# Licznik_mili_sekund.net
KiCad netlist of a schematic drawn in Altium Designer
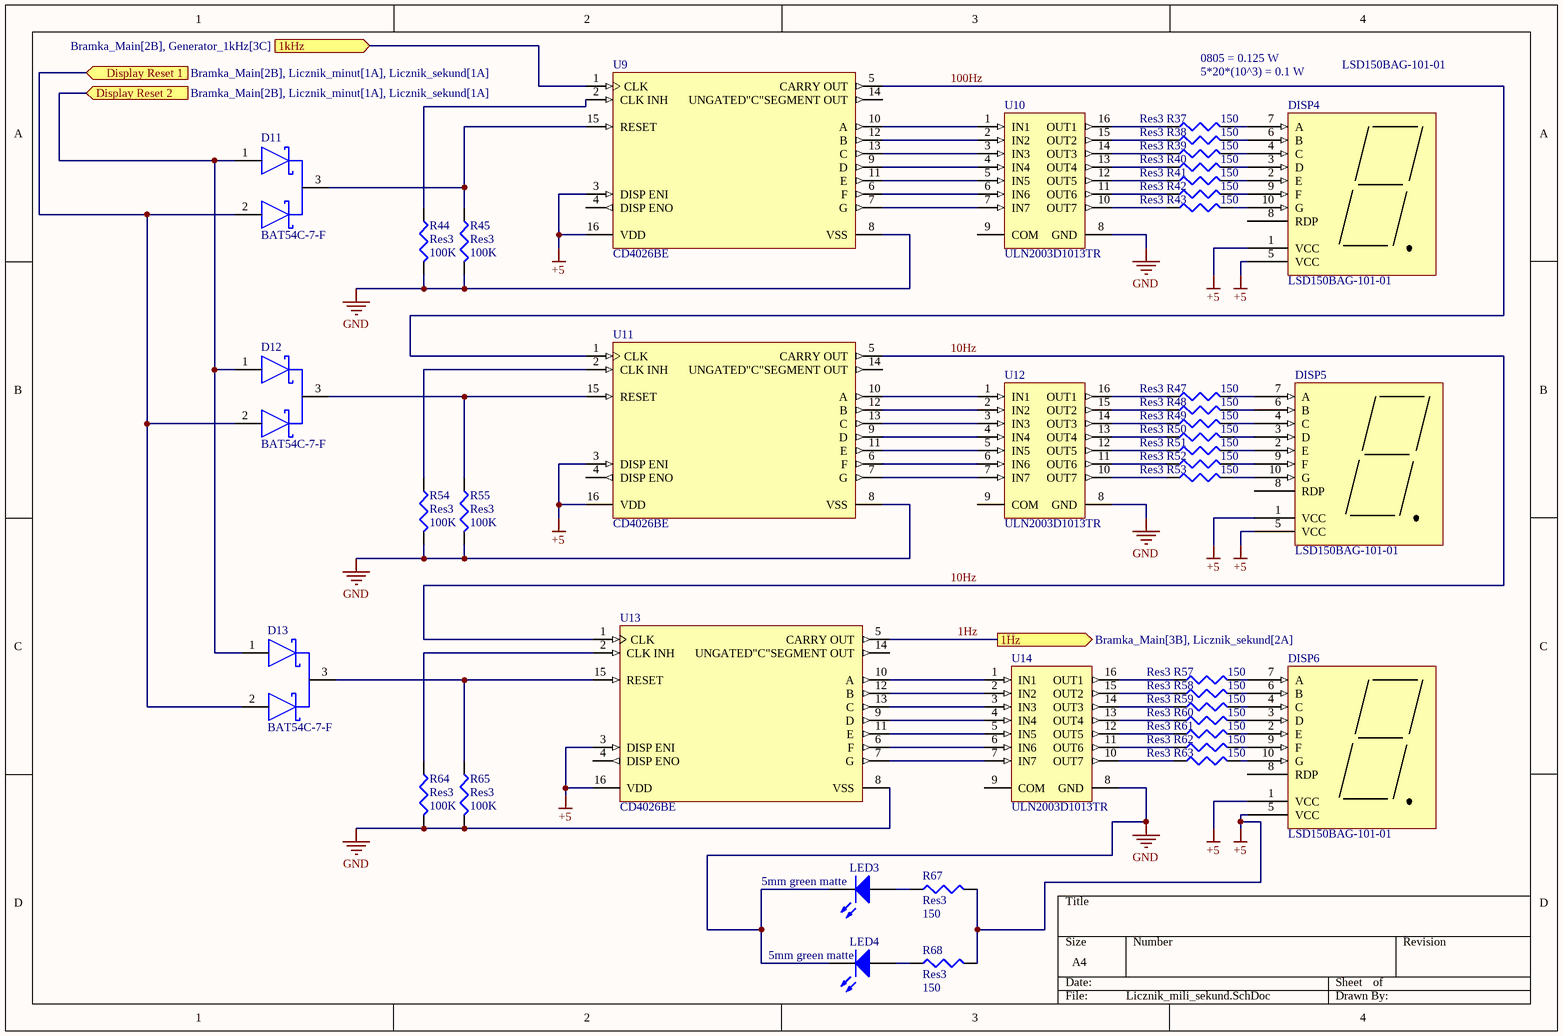
[diagram p0: Licznik_mili_sekund.SchDoc]

(export (version "E")
  (design (tool "Eeschema 10.0.6"))
  (components
    (comp (ref "D11")
      (value "BAT54C-7-F")
      (footprint "FP-SOT23-IPC_B")
      (description "DIODE ARRAY SCHOTTKY 30V SOT23-3")
      (libsource (lib "Altium Content Vault") (part "3eac2aa0c1ac86323ecc23460aa29c6"))
    )
    (comp (ref "D12")
      (value "BAT54C-7-F")
      (footprint "FP-SOT23-IPC_B")
      (description "DIODE ARRAY SCHOTTKY 30V SOT23-3")
      (libsource (lib "Altium Content Vault") (part "3eac2aa0c1ac86323ecc23460aa29c6"))
    )
    (comp (ref "D13")
      (value "BAT54C-7-F")
      (footprint "FP-SOT23-IPC_B")
      (description "DIODE ARRAY SCHOTTKY 30V SOT23-3")
      (libsource (lib "Altium Content Vault") (part "3eac2aa0c1ac86323ecc23460aa29c6"))
    )
    (comp (ref "DISP4")
      (value "LSD150BAG-101-01")
      (footprint "7 segment display")
      (description "7 segment display 1.5 inch")
      (libsource (lib "WUST") (part "LSD150BAG-101-01-Symbol-1"))
    )
    (comp (ref "DISP5")
      (value "LSD150BAG-101-01")
      (footprint "7 segment display")
      (description "7 segment display 1.5 inch")
      (libsource (lib "WUST") (part "LSD150BAG-101-01-Symbol-1"))
    )
    (comp (ref "DISP6")
      (value "LSD150BAG-101-01")
      (footprint "7 segment display")
      (description "7 segment display 1.5 inch")
      (libsource (lib "WUST") (part "LSD150BAG-101-01-Symbol-1"))
    )
    (comp (ref "LED3")
      (value "5mm green matte")
      (footprint "Type 5mm")
      (description "THT LED round mono-color color lens, WL-TMRW, Bright Green")
      (fields (field (name "PARTNUMBER") "151051VS04000") (field (name "MANUFACTURER") "Wuerth Elektronik"))
      (libsource (lib "Altium Content Vault") (part "WE-LED_K1A2-2"))
    )
    (comp (ref "LED4")
      (value "5mm green matte")
      (footprint "Type 5mm")
      (description "THT LED round mono-color color lens, WL-TMRW, Bright Green")
      (fields (field (name "PARTNUMBER") "151051VS04000") (field (name "MANUFACTURER") "Wuerth Elektronik"))
      (libsource (lib "Altium Content Vault") (part "WE-LED_K1A2-2"))
    )
    (comp (ref "R37")
      (value "Res3")
      (footprint "6-0805_M")
      (description "Resistor")
      (fields (field (name "ALTIUM_VALUE") "150") (field (name "PUBLISHER") "Altium Limited"))
      (libsource (lib "Miscellaneous Devices") (part "Res3"))
    )
    (comp (ref "R38")
      (value "Res3")
      (footprint "6-0805_M")
      (description "Resistor")
      (fields (field (name "ALTIUM_VALUE") "150") (field (name "PUBLISHER") "Altium Limited"))
      (libsource (lib "Miscellaneous Devices") (part "Res3"))
    )
    (comp (ref "R39")
      (value "Res3")
      (footprint "6-0805_M")
      (description "Resistor")
      (fields (field (name "ALTIUM_VALUE") "150") (field (name "PUBLISHER") "Altium Limited"))
      (libsource (lib "Miscellaneous Devices") (part "Res3"))
    )
    (comp (ref "R40")
      (value "Res3")
      (footprint "6-0805_M")
      (description "Resistor")
      (fields (field (name "ALTIUM_VALUE") "150") (field (name "PUBLISHER") "Altium Limited"))
      (libsource (lib "Miscellaneous Devices") (part "Res3"))
    )
    (comp (ref "R41")
      (value "Res3")
      (footprint "6-0805_M")
      (description "Resistor")
      (fields (field (name "ALTIUM_VALUE") "150") (field (name "PUBLISHER") "Altium Limited"))
      (libsource (lib "Miscellaneous Devices") (part "Res3"))
    )
    (comp (ref "R42")
      (value "Res3")
      (footprint "6-0805_M")
      (description "Resistor")
      (fields (field (name "ALTIUM_VALUE") "150") (field (name "PUBLISHER") "Altium Limited"))
      (libsource (lib "Miscellaneous Devices") (part "Res3"))
    )
    (comp (ref "R43")
      (value "Res3")
      (footprint "6-0805_M")
      (description "Resistor")
      (fields (field (name "ALTIUM_VALUE") "150") (field (name "PUBLISHER") "Altium Limited"))
      (libsource (lib "Miscellaneous Devices") (part "Res3"))
    )
    (comp (ref "R44")
      (value "Res3")
      (footprint "J1-0603")
      (description "Resistor")
      (fields (field (name "ALTIUM_VALUE") "100K") (field (name "PUBLISHER") "Altium Limited"))
      (libsource (lib "Miscellaneous Devices") (part "Res3"))
    )
    (comp (ref "R45")
      (value "Res3")
      (footprint "J1-0603")
      (description "Resistor")
      (fields (field (name "ALTIUM_VALUE") "100K") (field (name "PUBLISHER") "Altium Limited"))
      (libsource (lib "Miscellaneous Devices") (part "Res3"))
    )
    (comp (ref "R47")
      (value "Res3")
      (footprint "6-0805_M")
      (description "Resistor")
      (fields (field (name "ALTIUM_VALUE") "150") (field (name "PUBLISHER") "Altium Limited"))
      (libsource (lib "Miscellaneous Devices") (part "Res3"))
    )
    (comp (ref "R48")
      (value "Res3")
      (footprint "6-0805_M")
      (description "Resistor")
      (fields (field (name "ALTIUM_VALUE") "150") (field (name "PUBLISHER") "Altium Limited"))
      (libsource (lib "Miscellaneous Devices") (part "Res3"))
    )
    (comp (ref "R49")
      (value "Res3")
      (footprint "6-0805_M")
      (description "Resistor")
      (fields (field (name "ALTIUM_VALUE") "150") (field (name "PUBLISHER") "Altium Limited"))
      (libsource (lib "Miscellaneous Devices") (part "Res3"))
    )
    (comp (ref "R50")
      (value "Res3")
      (footprint "6-0805_M")
      (description "Resistor")
      (fields (field (name "ALTIUM_VALUE") "150") (field (name "PUBLISHER") "Altium Limited"))
      (libsource (lib "Miscellaneous Devices") (part "Res3"))
    )
    (comp (ref "R51")
      (value "Res3")
      (footprint "6-0805_M")
      (description "Resistor")
      (fields (field (name "ALTIUM_VALUE") "150") (field (name "PUBLISHER") "Altium Limited"))
      (libsource (lib "Miscellaneous Devices") (part "Res3"))
    )
    (comp (ref "R52")
      (value "Res3")
      (footprint "6-0805_M")
      (description "Resistor")
      (fields (field (name "ALTIUM_VALUE") "150") (field (name "PUBLISHER") "Altium Limited"))
      (libsource (lib "Miscellaneous Devices") (part "Res3"))
    )
    (comp (ref "R53")
      (value "Res3")
      (footprint "6-0805_M")
      (description "Resistor")
      (fields (field (name "ALTIUM_VALUE") "150") (field (name "PUBLISHER") "Altium Limited"))
      (libsource (lib "Miscellaneous Devices") (part "Res3"))
    )
    (comp (ref "R54")
      (value "Res3")
      (footprint "J1-0603")
      (description "Resistor")
      (fields (field (name "ALTIUM_VALUE") "100K") (field (name "PUBLISHER") "Altium Limited"))
      (libsource (lib "Miscellaneous Devices") (part "Res3"))
    )
    (comp (ref "R55")
      (value "Res3")
      (footprint "J1-0603")
      (description "Resistor")
      (fields (field (name "ALTIUM_VALUE") "100K") (field (name "PUBLISHER") "Altium Limited"))
      (libsource (lib "Miscellaneous Devices") (part "Res3"))
    )
    (comp (ref "R57")
      (value "Res3")
      (footprint "6-0805_M")
      (description "Resistor")
      (fields (field (name "ALTIUM_VALUE") "150") (field (name "PUBLISHER") "Altium Limited"))
      (libsource (lib "Miscellaneous Devices") (part "Res3"))
    )
    (comp (ref "R58")
      (value "Res3")
      (footprint "6-0805_M")
      (description "Resistor")
      (fields (field (name "ALTIUM_VALUE") "150") (field (name "PUBLISHER") "Altium Limited"))
      (libsource (lib "Miscellaneous Devices") (part "Res3"))
    )
    (comp (ref "R59")
      (value "Res3")
      (footprint "6-0805_M")
      (description "Resistor")
      (fields (field (name "ALTIUM_VALUE") "150") (field (name "PUBLISHER") "Altium Limited"))
      (libsource (lib "Miscellaneous Devices") (part "Res3"))
    )
    (comp (ref "R60")
      (value "Res3")
      (footprint "6-0805_M")
      (description "Resistor")
      (fields (field (name "ALTIUM_VALUE") "150") (field (name "PUBLISHER") "Altium Limited"))
      (libsource (lib "Miscellaneous Devices") (part "Res3"))
    )
    (comp (ref "R61")
      (value "Res3")
      (footprint "6-0805_M")
      (description "Resistor")
      (fields (field (name "ALTIUM_VALUE") "150") (field (name "PUBLISHER") "Altium Limited"))
      (libsource (lib "Miscellaneous Devices") (part "Res3"))
    )
    (comp (ref "R62")
      (value "Res3")
      (footprint "6-0805_M")
      (description "Resistor")
      (fields (field (name "ALTIUM_VALUE") "150") (field (name "PUBLISHER") "Altium Limited"))
      (libsource (lib "Miscellaneous Devices") (part "Res3"))
    )
    (comp (ref "R63")
      (value "Res3")
      (footprint "6-0805_M")
      (description "Resistor")
      (fields (field (name "ALTIUM_VALUE") "150") (field (name "PUBLISHER") "Altium Limited"))
      (libsource (lib "Miscellaneous Devices") (part "Res3"))
    )
    (comp (ref "R64")
      (value "Res3")
      (footprint "J1-0603")
      (description "Resistor")
      (fields (field (name "ALTIUM_VALUE") "100K") (field (name "PUBLISHER") "Altium Limited"))
      (libsource (lib "Miscellaneous Devices") (part "Res3"))
    )
    (comp (ref "R65")
      (value "Res3")
      (footprint "J1-0603")
      (description "Resistor")
      (fields (field (name "ALTIUM_VALUE") "100K") (field (name "PUBLISHER") "Altium Limited"))
      (libsource (lib "Miscellaneous Devices") (part "Res3"))
    )
    (comp (ref "R67")
      (value "Res3")
      (footprint "6-0805_M")
      (description "Resistor")
      (fields (field (name "ALTIUM_VALUE") "150") (field (name "PUBLISHER") "Altium Limited"))
      (libsource (lib "Miscellaneous Devices") (part "Res3"))
    )
    (comp (ref "R68")
      (value "Res3")
      (footprint "6-0805_M")
      (description "Resistor")
      (fields (field (name "ALTIUM_VALUE") "150") (field (name "PUBLISHER") "Altium Limited"))
      (libsource (lib "Miscellaneous Devices") (part "Res3"))
    )
    (comp (ref "U9")
      (value "CD4026BE")
      (footprint "N0016A")
      (fields
        (field (name "MANUFACTURER") "Texas Instruments")
        (field (name "GENERIC PART NUMBER") "CD4026B")
      )
      (libsource (lib "Altium Content Vault") (part "TI-CD4026B-16"))
    )
    (comp (ref "U10")
      (value "ULN2003D1013TR")
      (footprint "STM-SO-16_M")
      (fields (field (name "MANUFACTURER") "STMicroelectronics"))
      (libsource (lib "Altium Content Vault") (part "STM-ULN2003A-PDIP-16"))
    )
    (comp (ref "U11")
      (value "CD4026BE")
      (footprint "N0016A")
      (fields
        (field (name "MANUFACTURER") "Texas Instruments")
        (field (name "GENERIC PART NUMBER") "CD4026B")
      )
      (libsource (lib "Altium Content Vault") (part "TI-CD4026B-16"))
    )
    (comp (ref "U12")
      (value "ULN2003D1013TR")
      (footprint "STM-SO-16_M")
      (fields (field (name "MANUFACTURER") "STMicroelectronics"))
      (libsource (lib "Altium Content Vault") (part "STM-ULN2003A-PDIP-16"))
    )
    (comp (ref "U13")
      (value "CD4026BE")
      (footprint "N0016A")
      (fields
        (field (name "MANUFACTURER") "Texas Instruments")
        (field (name "GENERIC PART NUMBER") "CD4026B")
      )
      (libsource (lib "Altium Content Vault") (part "TI-CD4026B-16"))
    )
    (comp (ref "U14")
      (value "ULN2003D1013TR")
      (footprint "STM-SO-16_M")
      (fields (field (name "MANUFACTURER") "STMicroelectronics"))
      (libsource (lib "Altium Content Vault") (part "STM-ULN2003A-PDIP-16"))
    )
  )
  (nets
    (net (code "1") (name "+5") (class "Default")
      (node (ref "DISP4") (pin "1") (pinfunction "VCC_1") (pintype "power_in"))
      (node (ref "DISP4") (pin "5") (pinfunction "VCC_5") (pintype "power_in"))
      (node (ref "DISP5") (pin "1") (pinfunction "VCC_1") (pintype "power_in"))
      (node (ref "DISP5") (pin "5") (pinfunction "VCC_5") (pintype "power_in"))
      (node (ref "DISP6") (pin "1") (pinfunction "VCC_1") (pintype "power_in"))
      (node (ref "DISP6") (pin "5") (pinfunction "VCC_5") (pintype "power_in"))
      (node (ref "R67") (pin "2") (pinfunction "2_2") (pintype "passive"))
      (node (ref "R68") (pin "2") (pinfunction "2_2") (pintype "passive"))
      (node (ref "U11") (pin "16") (pinfunction "VDD_16") (pintype "power_in"))
      (node (ref "U11") (pin "3") (pinfunction "DISP_ENI_3") (pintype "input"))
      (node (ref "U13") (pin "16") (pinfunction "VDD_16") (pintype "power_in"))
      (node (ref "U13") (pin "3") (pinfunction "DISP_ENI_3") (pintype "input"))
      (node (ref "U9") (pin "16") (pinfunction "VDD_16") (pintype "power_in"))
      (node (ref "U9") (pin "3") (pinfunction "DISP_ENI_3") (pintype "input"))
    )
    (net (code "2") (name "/1Hz") (class "Default")
      (node (ref "U13") (pin "5") (pinfunction "CARRY_OUT_5") (pintype "output"))
    )
    (net (code "3") (name "/1kHz") (class "Default")
      (node (ref "U9") (pin "1") (pinfunction "CLK_1") (pintype "input"))
    )
    (net (code "4") (name "/10Hz") (class "Default")
      (node (ref "U11") (pin "5") (pinfunction "CARRY_OUT_5") (pintype "output"))
      (node (ref "U13") (pin "1") (pinfunction "CLK_1") (pintype "input"))
    )
    (net (code "5") (name "/100Hz") (class "Default")
      (node (ref "U11") (pin "1") (pinfunction "CLK_1") (pintype "input"))
      (node (ref "U9") (pin "5") (pinfunction "CARRY_OUT_5") (pintype "output"))
    )
    (net (code "6") (name "/Display Reset 1") (class "Default")
      (node (ref "D11") (pin "2") (pinfunction "2_ANODE_2") (pintype "passive"))
      (node (ref "D12") (pin "2") (pinfunction "2_ANODE_2") (pintype "passive"))
      (node (ref "D13") (pin "2") (pinfunction "2_ANODE_2") (pintype "passive"))
    )
    (net (code "7") (name "/Display Reset 2") (class "Default")
      (node (ref "D11") (pin "1") (pinfunction "1_ANODE_1") (pintype "passive"))
      (node (ref "D12") (pin "1") (pinfunction "1_ANODE_1") (pintype "passive"))
      (node (ref "D13") (pin "1") (pinfunction "1_ANODE_1") (pintype "passive"))
    )
    (net (code "8") (name "GND") (class "Default")
      (node (ref "LED3") (pin "1") (pinfunction "K_1") (pintype "passive"))
      (node (ref "LED4") (pin "1") (pinfunction "K_1") (pintype "passive"))
      (node (ref "R44") (pin "2") (pinfunction "2_2") (pintype "passive"))
      (node (ref "R45") (pin "2") (pinfunction "2_2") (pintype "passive"))
      (node (ref "R54") (pin "2") (pinfunction "2_2") (pintype "passive"))
      (node (ref "R55") (pin "2") (pinfunction "2_2") (pintype "passive"))
      (node (ref "R64") (pin "2") (pinfunction "2_2") (pintype "passive"))
      (node (ref "R65") (pin "2") (pinfunction "2_2") (pintype "passive"))
      (node (ref "U10") (pin "8") (pinfunction "GND_8") (pintype "power_in"))
      (node (ref "U11") (pin "8") (pinfunction "VSS_8") (pintype "power_in"))
      (node (ref "U12") (pin "8") (pinfunction "GND_8") (pintype "power_in"))
      (node (ref "U13") (pin "8") (pinfunction "VSS_8") (pintype "power_in"))
      (node (ref "U14") (pin "8") (pinfunction "GND_8") (pintype "power_in"))
      (node (ref "U9") (pin "8") (pinfunction "VSS_8") (pintype "power_in"))
    )
    (net (code "9") (name "Net-(D11-COMMON_CATHODE)") (class "Default")
      (node (ref "D11") (pin "3") (pinfunction "COMMON_CATHODE_3") (pintype "passive"))
      (node (ref "R45") (pin "1") (pinfunction "1_1") (pintype "passive"))
      (node (ref "U9") (pin "15") (pinfunction "RESET_15") (pintype "input"))
    )
    (net (code "10") (name "Net-(D12-COMMON_CATHODE)") (class "Default")
      (node (ref "D12") (pin "3") (pinfunction "COMMON_CATHODE_3") (pintype "passive"))
      (node (ref "R55") (pin "1") (pinfunction "1_1") (pintype "passive"))
      (node (ref "U11") (pin "15") (pinfunction "RESET_15") (pintype "input"))
    )
    (net (code "11") (name "Net-(D13-COMMON_CATHODE)") (class "Default")
      (node (ref "D13") (pin "3") (pinfunction "COMMON_CATHODE_3") (pintype "passive"))
      (node (ref "R65") (pin "1") (pinfunction "1_1") (pintype "passive"))
      (node (ref "U13") (pin "15") (pinfunction "RESET_15") (pintype "input"))
    )
    (net (code "12") (name "Net-(DISP4-A)") (class "Default")
      (node (ref "DISP4") (pin "7") (pinfunction "A_7") (pintype "input"))
      (node (ref "R37") (pin "2") (pinfunction "2_2") (pintype "passive"))
    )
    (net (code "13") (name "Net-(DISP4-B)") (class "Default")
      (node (ref "DISP4") (pin "6") (pinfunction "B_6") (pintype "input"))
      (node (ref "R38") (pin "2") (pinfunction "2_2") (pintype "passive"))
    )
    (net (code "14") (name "Net-(DISP4-C)") (class "Default")
      (node (ref "DISP4") (pin "4") (pinfunction "C_4") (pintype "input"))
      (node (ref "R39") (pin "2") (pinfunction "2_2") (pintype "passive"))
    )
    (net (code "15") (name "Net-(DISP4-D)") (class "Default")
      (node (ref "DISP4") (pin "3") (pinfunction "D_3") (pintype "input"))
      (node (ref "R40") (pin "2") (pinfunction "2_2") (pintype "passive"))
    )
    (net (code "16") (name "Net-(DISP4-E)") (class "Default")
      (node (ref "DISP4") (pin "2") (pinfunction "E_2") (pintype "input"))
      (node (ref "R41") (pin "2") (pinfunction "2_2") (pintype "passive"))
    )
    (net (code "17") (name "Net-(DISP4-F)") (class "Default")
      (node (ref "DISP4") (pin "9") (pinfunction "F_9") (pintype "input"))
      (node (ref "R42") (pin "2") (pinfunction "2_2") (pintype "passive"))
    )
    (net (code "18") (name "Net-(DISP4-G)") (class "Default")
      (node (ref "DISP4") (pin "10") (pinfunction "G_10") (pintype "input"))
      (node (ref "R43") (pin "2") (pinfunction "2_2") (pintype "passive"))
    )
    (net (code "19") (name "Net-(DISP5-A)") (class "Default")
      (node (ref "DISP5") (pin "7") (pinfunction "A_7") (pintype "input"))
      (node (ref "R47") (pin "2") (pinfunction "2_2") (pintype "passive"))
    )
    (net (code "20") (name "Net-(DISP5-B)") (class "Default")
      (node (ref "DISP5") (pin "6") (pinfunction "B_6") (pintype "input"))
      (node (ref "R48") (pin "2") (pinfunction "2_2") (pintype "passive"))
    )
    (net (code "21") (name "Net-(DISP5-C)") (class "Default")
      (node (ref "DISP5") (pin "4") (pinfunction "C_4") (pintype "input"))
      (node (ref "R49") (pin "2") (pinfunction "2_2") (pintype "passive"))
    )
    (net (code "22") (name "Net-(DISP5-D)") (class "Default")
      (node (ref "DISP5") (pin "3") (pinfunction "D_3") (pintype "input"))
      (node (ref "R50") (pin "2") (pinfunction "2_2") (pintype "passive"))
    )
    (net (code "23") (name "Net-(DISP5-E)") (class "Default")
      (node (ref "DISP5") (pin "2") (pinfunction "E_2") (pintype "input"))
      (node (ref "R51") (pin "2") (pinfunction "2_2") (pintype "passive"))
    )
    (net (code "24") (name "Net-(DISP5-F)") (class "Default")
      (node (ref "DISP5") (pin "9") (pinfunction "F_9") (pintype "input"))
      (node (ref "R52") (pin "2") (pinfunction "2_2") (pintype "passive"))
    )
    (net (code "25") (name "Net-(DISP5-G)") (class "Default")
      (node (ref "DISP5") (pin "10") (pinfunction "G_10") (pintype "input"))
      (node (ref "R53") (pin "2") (pinfunction "2_2") (pintype "passive"))
    )
    (net (code "26") (name "Net-(DISP6-A)") (class "Default")
      (node (ref "DISP6") (pin "7") (pinfunction "A_7") (pintype "input"))
      (node (ref "R57") (pin "2") (pinfunction "2_2") (pintype "passive"))
    )
    (net (code "27") (name "Net-(DISP6-B)") (class "Default")
      (node (ref "DISP6") (pin "6") (pinfunction "B_6") (pintype "input"))
      (node (ref "R58") (pin "2") (pinfunction "2_2") (pintype "passive"))
    )
    (net (code "28") (name "Net-(DISP6-C)") (class "Default")
      (node (ref "DISP6") (pin "4") (pinfunction "C_4") (pintype "input"))
      (node (ref "R59") (pin "2") (pinfunction "2_2") (pintype "passive"))
    )
    (net (code "29") (name "Net-(DISP6-D)") (class "Default")
      (node (ref "DISP6") (pin "3") (pinfunction "D_3") (pintype "input"))
      (node (ref "R60") (pin "2") (pinfunction "2_2") (pintype "passive"))
    )
    (net (code "30") (name "Net-(DISP6-E)") (class "Default")
      (node (ref "DISP6") (pin "2") (pinfunction "E_2") (pintype "input"))
      (node (ref "R61") (pin "2") (pinfunction "2_2") (pintype "passive"))
    )
    (net (code "31") (name "Net-(DISP6-F)") (class "Default")
      (node (ref "DISP6") (pin "9") (pinfunction "F_9") (pintype "input"))
      (node (ref "R62") (pin "2") (pinfunction "2_2") (pintype "passive"))
    )
    (net (code "32") (name "Net-(DISP6-G)") (class "Default")
      (node (ref "DISP6") (pin "10") (pinfunction "G_10") (pintype "input"))
      (node (ref "R63") (pin "2") (pinfunction "2_2") (pintype "passive"))
    )
    (net (code "33") (name "Net-(LED3-A)") (class "Default")
      (node (ref "LED3") (pin "2") (pinfunction "A_2") (pintype "passive"))
      (node (ref "R67") (pin "1") (pinfunction "1_1") (pintype "passive"))
    )
    (net (code "34") (name "Net-(LED4-A)") (class "Default")
      (node (ref "LED4") (pin "2") (pinfunction "A_2") (pintype "passive"))
      (node (ref "R68") (pin "1") (pinfunction "1_1") (pintype "passive"))
    )
    (net (code "35") (name "Net-(U9-CLK_INH)") (class "Default")
      (node (ref "R44") (pin "1") (pinfunction "1_1") (pintype "passive"))
      (node (ref "U9") (pin "2") (pinfunction "CLK_INH_2") (pintype "input"))
    )
    (net (code "36") (name "Net-(U10-IN1)") (class "Default")
      (node (ref "U10") (pin "1") (pinfunction "IN1_1") (pintype "input"))
      (node (ref "U9") (pin "10") (pinfunction "A_10") (pintype "output"))
    )
    (net (code "37") (name "Net-(U10-IN2)") (class "Default")
      (node (ref "U10") (pin "2") (pinfunction "IN2_2") (pintype "input"))
      (node (ref "U9") (pin "12") (pinfunction "B_12") (pintype "output"))
    )
    (net (code "38") (name "Net-(U10-IN3)") (class "Default")
      (node (ref "U10") (pin "3") (pinfunction "IN3_3") (pintype "input"))
      (node (ref "U9") (pin "13") (pinfunction "C_13") (pintype "output"))
    )
    (net (code "39") (name "Net-(U10-IN4)") (class "Default")
      (node (ref "U10") (pin "4") (pinfunction "IN4_4") (pintype "input"))
      (node (ref "U9") (pin "9") (pinfunction "D_9") (pintype "output"))
    )
    (net (code "40") (name "Net-(U10-IN5)") (class "Default")
      (node (ref "U10") (pin "5") (pinfunction "IN5_5") (pintype "input"))
      (node (ref "U9") (pin "11") (pinfunction "E_11") (pintype "output"))
    )
    (net (code "41") (name "Net-(U10-IN6)") (class "Default")
      (node (ref "U10") (pin "6") (pinfunction "IN6_6") (pintype "input"))
      (node (ref "U9") (pin "6") (pinfunction "F_6") (pintype "output"))
    )
    (net (code "42") (name "Net-(U10-IN7)") (class "Default")
      (node (ref "U10") (pin "7") (pinfunction "IN7_7") (pintype "input"))
      (node (ref "U9") (pin "7") (pinfunction "G_7") (pintype "output"))
    )
    (net (code "43") (name "Net-(U10-OUT1)") (class "Default")
      (node (ref "R37") (pin "1") (pinfunction "1_1") (pintype "passive"))
      (node (ref "U10") (pin "16") (pinfunction "OUT1_16") (pintype "output"))
    )
    (net (code "44") (name "Net-(U10-OUT2)") (class "Default")
      (node (ref "R38") (pin "1") (pinfunction "1_1") (pintype "passive"))
      (node (ref "U10") (pin "15") (pinfunction "OUT2_15") (pintype "output"))
    )
    (net (code "45") (name "Net-(U10-OUT3)") (class "Default")
      (node (ref "R39") (pin "1") (pinfunction "1_1") (pintype "passive"))
      (node (ref "U10") (pin "14") (pinfunction "OUT3_14") (pintype "output"))
    )
    (net (code "46") (name "Net-(U10-OUT4)") (class "Default")
      (node (ref "R40") (pin "1") (pinfunction "1_1") (pintype "passive"))
      (node (ref "U10") (pin "13") (pinfunction "OUT4_13") (pintype "output"))
    )
    (net (code "47") (name "Net-(U10-OUT5)") (class "Default")
      (node (ref "R41") (pin "1") (pinfunction "1_1") (pintype "passive"))
      (node (ref "U10") (pin "12") (pinfunction "OUT5_12") (pintype "output"))
    )
    (net (code "48") (name "Net-(U10-OUT6)") (class "Default")
      (node (ref "R42") (pin "1") (pinfunction "1_1") (pintype "passive"))
      (node (ref "U10") (pin "11") (pinfunction "OUT6_11") (pintype "output"))
    )
    (net (code "49") (name "Net-(U10-OUT7)") (class "Default")
      (node (ref "R43") (pin "1") (pinfunction "1_1") (pintype "passive"))
      (node (ref "U10") (pin "10") (pinfunction "OUT7_10") (pintype "output"))
    )
    (net (code "50") (name "Net-(U11-A)") (class "Default")
      (node (ref "U11") (pin "10") (pinfunction "A_10") (pintype "output"))
      (node (ref "U12") (pin "1") (pinfunction "IN1_1") (pintype "input"))
    )
    (net (code "51") (name "Net-(U11-B)") (class "Default")
      (node (ref "U11") (pin "12") (pinfunction "B_12") (pintype "output"))
      (node (ref "U12") (pin "2") (pinfunction "IN2_2") (pintype "input"))
    )
    (net (code "52") (name "Net-(U11-C)") (class "Default")
      (node (ref "U11") (pin "13") (pinfunction "C_13") (pintype "output"))
      (node (ref "U12") (pin "3") (pinfunction "IN3_3") (pintype "input"))
    )
    (net (code "53") (name "Net-(U11-CLK_INH)") (class "Default")
      (node (ref "R54") (pin "1") (pinfunction "1_1") (pintype "passive"))
      (node (ref "U11") (pin "2") (pinfunction "CLK_INH_2") (pintype "input"))
    )
    (net (code "54") (name "Net-(U11-D)") (class "Default")
      (node (ref "U11") (pin "9") (pinfunction "D_9") (pintype "output"))
      (node (ref "U12") (pin "4") (pinfunction "IN4_4") (pintype "input"))
    )
    (net (code "55") (name "Net-(U11-E)") (class "Default")
      (node (ref "U11") (pin "11") (pinfunction "E_11") (pintype "output"))
      (node (ref "U12") (pin "5") (pinfunction "IN5_5") (pintype "input"))
    )
    (net (code "56") (name "Net-(U11-F)") (class "Default")
      (node (ref "U11") (pin "6") (pinfunction "F_6") (pintype "output"))
      (node (ref "U12") (pin "6") (pinfunction "IN6_6") (pintype "input"))
    )
    (net (code "57") (name "Net-(U11-G)") (class "Default")
      (node (ref "U11") (pin "7") (pinfunction "G_7") (pintype "output"))
      (node (ref "U12") (pin "7") (pinfunction "IN7_7") (pintype "input"))
    )
    (net (code "58") (name "Net-(U12-OUT1)") (class "Default")
      (node (ref "R47") (pin "1") (pinfunction "1_1") (pintype "passive"))
      (node (ref "U12") (pin "16") (pinfunction "OUT1_16") (pintype "output"))
    )
    (net (code "59") (name "Net-(U12-OUT2)") (class "Default")
      (node (ref "R48") (pin "1") (pinfunction "1_1") (pintype "passive"))
      (node (ref "U12") (pin "15") (pinfunction "OUT2_15") (pintype "output"))
    )
    (net (code "60") (name "Net-(U12-OUT3)") (class "Default")
      (node (ref "R49") (pin "1") (pinfunction "1_1") (pintype "passive"))
      (node (ref "U12") (pin "14") (pinfunction "OUT3_14") (pintype "output"))
    )
    (net (code "61") (name "Net-(U12-OUT4)") (class "Default")
      (node (ref "R50") (pin "1") (pinfunction "1_1") (pintype "passive"))
      (node (ref "U12") (pin "13") (pinfunction "OUT4_13") (pintype "output"))
    )
    (net (code "62") (name "Net-(U12-OUT5)") (class "Default")
      (node (ref "R51") (pin "1") (pinfunction "1_1") (pintype "passive"))
      (node (ref "U12") (pin "12") (pinfunction "OUT5_12") (pintype "output"))
    )
    (net (code "63") (name "Net-(U12-OUT6)") (class "Default")
      (node (ref "R52") (pin "1") (pinfunction "1_1") (pintype "passive"))
      (node (ref "U12") (pin "11") (pinfunction "OUT6_11") (pintype "output"))
    )
    (net (code "64") (name "Net-(U12-OUT7)") (class "Default")
      (node (ref "R53") (pin "1") (pinfunction "1_1") (pintype "passive"))
      (node (ref "U12") (pin "10") (pinfunction "OUT7_10") (pintype "output"))
    )
    (net (code "65") (name "Net-(U13-A)") (class "Default")
      (node (ref "U13") (pin "10") (pinfunction "A_10") (pintype "output"))
      (node (ref "U14") (pin "1") (pinfunction "IN1_1") (pintype "input"))
    )
    (net (code "66") (name "Net-(U13-B)") (class "Default")
      (node (ref "U13") (pin "12") (pinfunction "B_12") (pintype "output"))
      (node (ref "U14") (pin "2") (pinfunction "IN2_2") (pintype "input"))
    )
    (net (code "67") (name "Net-(U13-C)") (class "Default")
      (node (ref "U13") (pin "13") (pinfunction "C_13") (pintype "output"))
      (node (ref "U14") (pin "3") (pinfunction "IN3_3") (pintype "input"))
    )
    (net (code "68") (name "Net-(U13-CLK_INH)") (class "Default")
      (node (ref "R64") (pin "1") (pinfunction "1_1") (pintype "passive"))
      (node (ref "U13") (pin "2") (pinfunction "CLK_INH_2") (pintype "input"))
    )
    (net (code "69") (name "Net-(U13-D)") (class "Default")
      (node (ref "U13") (pin "9") (pinfunction "D_9") (pintype "output"))
      (node (ref "U14") (pin "4") (pinfunction "IN4_4") (pintype "input"))
    )
    (net (code "70") (name "Net-(U13-E)") (class "Default")
      (node (ref "U13") (pin "11") (pinfunction "E_11") (pintype "output"))
      (node (ref "U14") (pin "5") (pinfunction "IN5_5") (pintype "input"))
    )
    (net (code "71") (name "Net-(U13-F)") (class "Default")
      (node (ref "U13") (pin "6") (pinfunction "F_6") (pintype "output"))
      (node (ref "U14") (pin "6") (pinfunction "IN6_6") (pintype "input"))
    )
    (net (code "72") (name "Net-(U13-G)") (class "Default")
      (node (ref "U13") (pin "7") (pinfunction "G_7") (pintype "output"))
      (node (ref "U14") (pin "7") (pinfunction "IN7_7") (pintype "input"))
    )
    (net (code "73") (name "Net-(U14-OUT1)") (class "Default")
      (node (ref "R57") (pin "1") (pinfunction "1_1") (pintype "passive"))
      (node (ref "U14") (pin "16") (pinfunction "OUT1_16") (pintype "output"))
    )
    (net (code "74") (name "Net-(U14-OUT2)") (class "Default")
      (node (ref "R58") (pin "1") (pinfunction "1_1") (pintype "passive"))
      (node (ref "U14") (pin "15") (pinfunction "OUT2_15") (pintype "output"))
    )
    (net (code "75") (name "Net-(U14-OUT3)") (class "Default")
      (node (ref "R59") (pin "1") (pinfunction "1_1") (pintype "passive"))
      (node (ref "U14") (pin "14") (pinfunction "OUT3_14") (pintype "output"))
    )
    (net (code "76") (name "Net-(U14-OUT4)") (class "Default")
      (node (ref "R60") (pin "1") (pinfunction "1_1") (pintype "passive"))
      (node (ref "U14") (pin "13") (pinfunction "OUT4_13") (pintype "output"))
    )
    (net (code "77") (name "Net-(U14-OUT5)") (class "Default")
      (node (ref "R61") (pin "1") (pinfunction "1_1") (pintype "passive"))
      (node (ref "U14") (pin "12") (pinfunction "OUT5_12") (pintype "output"))
    )
    (net (code "78") (name "Net-(U14-OUT6)") (class "Default")
      (node (ref "R62") (pin "1") (pinfunction "1_1") (pintype "passive"))
      (node (ref "U14") (pin "11") (pinfunction "OUT6_11") (pintype "output"))
    )
    (net (code "79") (name "Net-(U14-OUT7)") (class "Default")
      (node (ref "R63") (pin "1") (pinfunction "1_1") (pintype "passive"))
      (node (ref "U14") (pin "10") (pinfunction "OUT7_10") (pintype "output"))
    )
    (net (code "80") (name "unconnected-(DISP4-RDP-Pad8)") (class "Default")
      (node (ref "DISP4") (pin "8") (pinfunction "RDP_8") (pintype "passive"))
    )
    (net (code "81") (name "unconnected-(DISP5-RDP-Pad8)") (class "Default")
      (node (ref "DISP5") (pin "8") (pinfunction "RDP_8") (pintype "passive"))
    )
    (net (code "82") (name "unconnected-(DISP6-RDP-Pad8)") (class "Default")
      (node (ref "DISP6") (pin "8") (pinfunction "RDP_8") (pintype "passive"))
    )
    (net (code "83") (name "unconnected-(U9-DISP_ENO-Pad4)") (class "Default")
      (node (ref "U9") (pin "4") (pinfunction "DISP_ENO_4") (pintype "output"))
    )
    (net (code "84") (name "unconnected-(U9-UNGATED\"C\"SEGMENT_OUT-Pad14)") (class "Default")
      (node (ref "U9") (pin "14") (pinfunction "UNGATED\"C\"SEGMENT_OUT_14") (pintype "output"))
    )
    (net (code "85") (name "unconnected-(U10-COM-Pad9)") (class "Default")
      (node (ref "U10") (pin "9") (pinfunction "COM_9") (pintype "passive"))
    )
    (net (code "86") (name "unconnected-(U11-DISP_ENO-Pad4)") (class "Default")
      (node (ref "U11") (pin "4") (pinfunction "DISP_ENO_4") (pintype "output"))
    )
    (net (code "87") (name "unconnected-(U11-UNGATED\"C\"SEGMENT_OUT-Pad14)") (class "Default")
      (node (ref "U11") (pin "14") (pinfunction "UNGATED\"C\"SEGMENT_OUT_14") (pintype "output"))
    )
    (net (code "88") (name "unconnected-(U12-COM-Pad9)") (class "Default")
      (node (ref "U12") (pin "9") (pinfunction "COM_9") (pintype "passive"))
    )
    (net (code "89") (name "unconnected-(U13-DISP_ENO-Pad4)") (class "Default")
      (node (ref "U13") (pin "4") (pinfunction "DISP_ENO_4") (pintype "output"))
    )
    (net (code "90") (name "unconnected-(U13-UNGATED\"C\"SEGMENT_OUT-Pad14)") (class "Default")
      (node (ref "U13") (pin "14") (pinfunction "UNGATED\"C\"SEGMENT_OUT_14") (pintype "output"))
    )
    (net (code "91") (name "unconnected-(U14-COM-Pad9)") (class "Default")
      (node (ref "U14") (pin "9") (pinfunction "COM_9") (pintype "passive"))
    )
  )
)
